# 328pv3.net
KiCad netlist of a schematic drawn in EAGLE
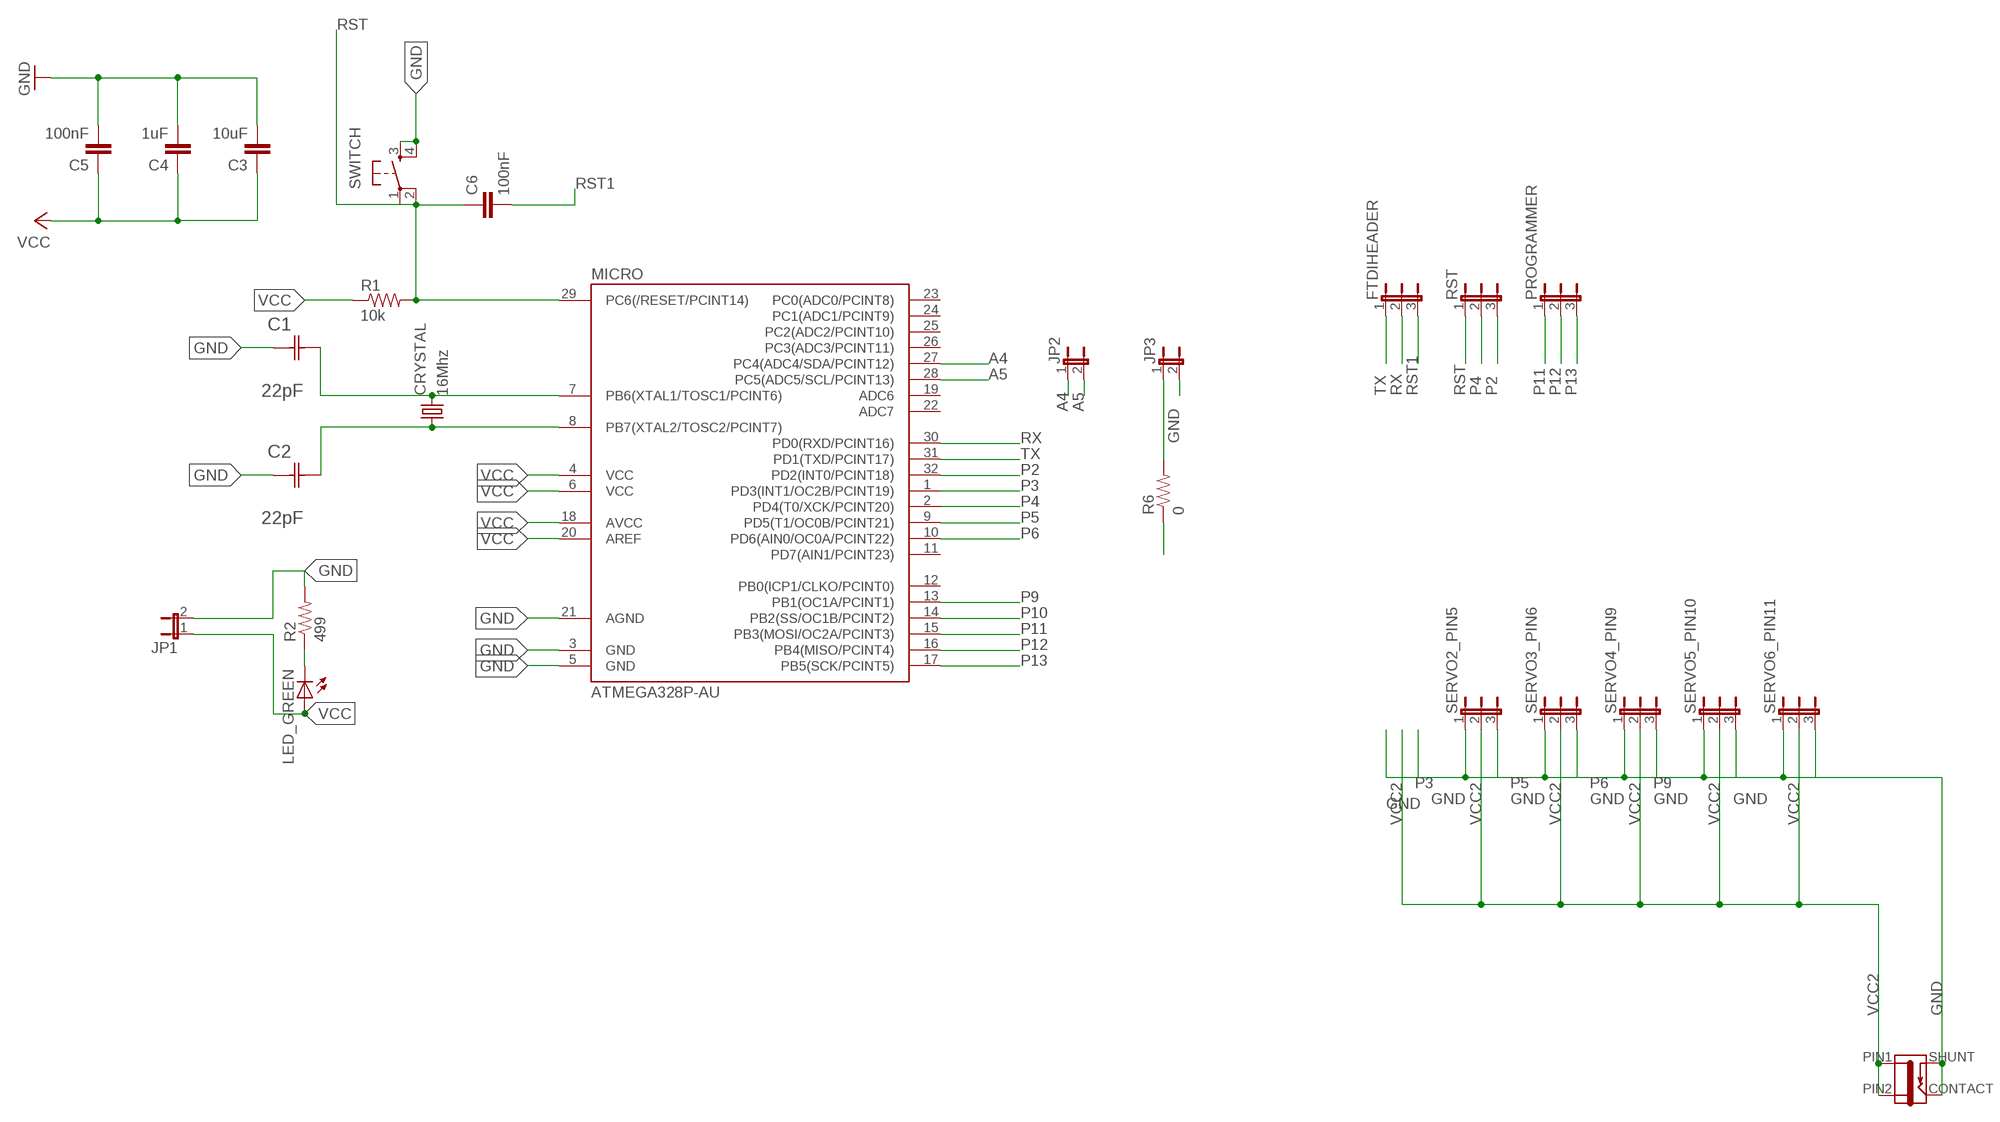
[diagram p0: schematic, sheet 1]

(export (version "E")
  (design (tool "Eeschema 10.0.6"))
  (components
    (comp (ref "C1")
      (value "22pF")
      (footprint "eagle-import:CAPC3216X178N")
      (fields (field (name "MPN") "0612ZC225MAT2A") (field (name "TOLERANCE") "±20%"))
      (libsource (lib "eagle-import") (part "0612ZC225MAT2A"))
    )
    (comp (ref "C2")
      (value "22pF")
      (footprint "eagle-import:CAPC3216X178N")
      (fields (field (name "MPN") "0612ZC225MAT2A") (field (name "TOLERANCE") "±20%"))
      (libsource (lib "eagle-import") (part "0612ZC225MAT2A"))
    )
    (comp (ref "C3")
      (value "10uF")
      (footprint "eagle-import:1206")
      (libsource (lib "eagle-import") (part "CAP1206"))
    )
    (comp (ref "C4")
      (value "1uF")
      (footprint "eagle-import:1206")
      (libsource (lib "eagle-import") (part "CAP1206"))
    )
    (comp (ref "C5")
      (value "100nF")
      (footprint "eagle-import:1206")
      (libsource (lib "eagle-import") (part "CAP1206"))
    )
    (comp (ref "C6")
      (value "100nF")
      (footprint "eagle-import:1206")
      (libsource (lib "eagle-import") (part "CAP1206"))
    )
    (comp (ref "CRYSTAL")
      (value "16Mhz")
      (footprint "eagle-import:CSM-7X-DU")
      (libsource (lib "eagle-import") (part "CSM-7X-DU"))
    )
    (comp (ref "FTDIHEADER")
      (value "JP2E")
      (footprint "eagle-import:JP2")
      (libsource (lib "eagle-import") (part "JP2E"))
    )
    (comp (ref "J1")
      (value "JACK-2.1MM")
      (footprint "eagle-import:PJ-002AH-SMT")
      (libsource (lib "eagle-import") (part "JACK-2.1MM"))
    )
    (comp (ref "JP1")
      (value "JP1E")
      (footprint "eagle-import:JP1")
      (libsource (lib "eagle-import") (part "JP1E"))
    )
    (comp (ref "JP2")
      (value "JP1E")
      (footprint "eagle-import:JP1")
      (libsource (lib "eagle-import") (part "JP1E"))
    )
    (comp (ref "JP3")
      (value "JP1E")
      (footprint "eagle-import:JP1")
      (libsource (lib "eagle-import") (part "JP1E"))
    )
    (comp (ref "LED_GREEN")
      (value "LED1206")
      (footprint "eagle-import:1206")
      (libsource (lib "eagle-import") (part "LED1206"))
    )
    (comp (ref "MICRO")
      (value "ATMEGA328P-AU")
      (footprint "eagle-import:TQFP32-08")
      (libsource (lib "eagle-import") (part "ATMEGA48/88/168-AU"))
    )
    (comp (ref "PROGRAMMER")
      (value "JP2E")
      (footprint "eagle-import:JP2")
      (libsource (lib "eagle-import") (part "JP2E"))
    )
    (comp (ref "R1")
      (value "10k")
      (footprint "eagle-import:1206")
      (libsource (lib "eagle-import") (part "RESISTOR1206"))
    )
    (comp (ref "R2")
      (value "499")
      (footprint "eagle-import:1206")
      (libsource (lib "eagle-import") (part "RESISTOR1206"))
    )
    (comp (ref "R6")
      (value "0")
      (footprint "eagle-import:1206")
      (libsource (lib "eagle-import") (part "RESISTOR1206"))
    )
    (comp (ref "RST")
      (value "JP2E")
      (footprint "eagle-import:JP2")
      (libsource (lib "eagle-import") (part "JP2E"))
    )
    (comp (ref "SERVO2_PIN5")
      (value "JP2E")
      (footprint "eagle-import:JP2")
      (libsource (lib "eagle-import") (part "JP2E"))
    )
    (comp (ref "SERVO3_PIN6")
      (value "JP2E")
      (footprint "eagle-import:JP2")
      (libsource (lib "eagle-import") (part "JP2E"))
    )
    (comp (ref "SERVO4_PIN9")
      (value "JP2E")
      (footprint "eagle-import:JP2")
      (libsource (lib "eagle-import") (part "JP2E"))
    )
    (comp (ref "SERVO5_PIN10")
      (value "JP2E")
      (footprint "eagle-import:JP2")
      (libsource (lib "eagle-import") (part "JP2E"))
    )
    (comp (ref "SERVO6_PIN11")
      (value "JP2E")
      (footprint "eagle-import:JP2")
      (libsource (lib "eagle-import") (part "JP2E"))
    )
    (comp (ref "SWITCH")
      (value "6MM_SWITCH6MM_SWITCH")
      (footprint "eagle-import:6MM_SWITCH")
      (libsource (lib "eagle-import") (part "6MM_SWITCH6MM_SWITCH"))
    )
  )
  (nets
    (net (code "1") (name "/A4") (class "Default")
      (node (ref "JP2") (pin "1") (pinfunction "1_1") (pintype "passive"))
      (node (ref "MICRO") (pin "27") (pinfunction "PC4(ADC4/SDA/PCINT12)_27") (pintype "bidirectional"))
    )
    (net (code "2") (name "/A5") (class "Default")
      (node (ref "JP2") (pin "2") (pinfunction "2_2") (pintype "passive"))
      (node (ref "MICRO") (pin "28") (pinfunction "PC5(ADC5/SCL/PCINT13)_28") (pintype "bidirectional"))
    )
    (net (code "3") (name "/P2") (class "Default")
      (node (ref "MICRO") (pin "32") (pinfunction "PD2(INT0/PCINT18)_32") (pintype "bidirectional"))
      (node (ref "RST") (pin "3") (pinfunction "3_3") (pintype "passive"))
    )
    (net (code "4") (name "/P3") (class "Default")
      (node (ref "MICRO") (pin "1") (pinfunction "PD3(INT1/OC2B/PCINT19)_1") (pintype "bidirectional"))
    )
    (net (code "5") (name "/P4") (class "Default")
      (node (ref "MICRO") (pin "2") (pinfunction "PD4(T0/XCK/PCINT20)_2") (pintype "bidirectional"))
      (node (ref "RST") (pin "2") (pinfunction "2_2") (pintype "passive"))
    )
    (net (code "6") (name "/P5") (class "Default")
      (node (ref "MICRO") (pin "9") (pinfunction "PD5(T1/OC0B/PCINT21)_9") (pintype "bidirectional"))
      (node (ref "SERVO2_PIN5") (pin "3") (pinfunction "3_3") (pintype "passive"))
    )
    (net (code "7") (name "/P6") (class "Default")
      (node (ref "MICRO") (pin "10") (pinfunction "PD6(AIN0/OC0A/PCINT22)_10") (pintype "bidirectional"))
      (node (ref "SERVO3_PIN6") (pin "3") (pinfunction "3_3") (pintype "passive"))
    )
    (net (code "8") (name "/P9") (class "Default")
      (node (ref "MICRO") (pin "13") (pinfunction "PB1(OC1A/PCINT1)_13") (pintype "bidirectional"))
      (node (ref "SERVO4_PIN9") (pin "3") (pinfunction "3_3") (pintype "passive"))
    )
    (net (code "9") (name "/P10") (class "Default")
      (node (ref "MICRO") (pin "14") (pinfunction "PB2(SS/OC1B/PCINT2)_14") (pintype "bidirectional"))
      (node (ref "SERVO5_PIN10") (pin "3") (pinfunction "3_3") (pintype "passive"))
    )
    (net (code "10") (name "/P11") (class "Default")
      (node (ref "MICRO") (pin "15") (pinfunction "PB3(MOSI/OC2A/PCINT3)_15") (pintype "bidirectional"))
      (node (ref "PROGRAMMER") (pin "1") (pinfunction "1_1") (pintype "passive"))
      (node (ref "SERVO6_PIN11") (pin "3") (pinfunction "3_3") (pintype "passive"))
    )
    (net (code "11") (name "/P12") (class "Default")
      (node (ref "MICRO") (pin "16") (pinfunction "PB4(MISO/PCINT4)_16") (pintype "bidirectional"))
      (node (ref "PROGRAMMER") (pin "2") (pinfunction "2_2") (pintype "passive"))
    )
    (net (code "12") (name "/P13") (class "Default")
      (node (ref "MICRO") (pin "17") (pinfunction "PB5(SCK/PCINT5)_17") (pintype "bidirectional"))
      (node (ref "PROGRAMMER") (pin "3") (pinfunction "3_3") (pintype "passive"))
    )
    (net (code "13") (name "/RST") (class "Default")
      (node (ref "C6") (pin "1") (pinfunction "1_1") (pintype "passive"))
      (node (ref "MICRO") (pin "29") (pinfunction "PC6(/RESET/PCINT14)_29") (pintype "bidirectional"))
      (node (ref "R1") (pin "2") (pinfunction "2_2") (pintype "passive"))
      (node (ref "RST") (pin "1") (pinfunction "1_1") (pintype "passive"))
      (node (ref "SWITCH") (pin "1") (pinfunction "P_1") (pintype "passive"))
      (node (ref "SWITCH") (pin "2") (pinfunction "P1_2") (pintype "passive"))
    )
    (net (code "14") (name "/RST1") (class "Default")
      (node (ref "C6") (pin "2") (pinfunction "2_2") (pintype "passive"))
      (node (ref "FTDIHEADER") (pin "3") (pinfunction "3_3") (pintype "passive"))
    )
    (net (code "15") (name "/RX") (class "Default")
      (node (ref "FTDIHEADER") (pin "2") (pinfunction "2_2") (pintype "passive"))
      (node (ref "MICRO") (pin "30") (pinfunction "PD0(RXD/PCINT16)_30") (pintype "bidirectional"))
    )
    (net (code "16") (name "/TX") (class "Default")
      (node (ref "FTDIHEADER") (pin "1") (pinfunction "1_1") (pintype "passive"))
      (node (ref "MICRO") (pin "31") (pinfunction "PD1(TXD/PCINT17)_31") (pintype "bidirectional"))
    )
    (net (code "17") (name "/VCC2") (class "Default")
      (node (ref "J1") (pin "PIN1") (pinfunction "PIN1_PIN1") (pintype "power_in"))
      (node (ref "J1") (pin "PIN2") (pinfunction "PIN2_PIN2") (pintype "power_in"))
      (node (ref "R6") (pin "1") (pinfunction "1_1") (pintype "passive"))
      (node (ref "SERVO2_PIN5") (pin "2") (pinfunction "2_2") (pintype "passive"))
      (node (ref "SERVO3_PIN6") (pin "2") (pinfunction "2_2") (pintype "passive"))
      (node (ref "SERVO4_PIN9") (pin "2") (pinfunction "2_2") (pintype "passive"))
      (node (ref "SERVO5_PIN10") (pin "2") (pinfunction "2_2") (pintype "passive"))
      (node (ref "SERVO6_PIN11") (pin "2") (pinfunction "2_2") (pintype "passive"))
    )
    (net (code "18") (name "GND") (class "Default")
      (node (ref "C1") (pin "1") (pinfunction "C1_1") (pintype "passive"))
      (node (ref "C2") (pin "1") (pinfunction "C1_1") (pintype "passive"))
      (node (ref "C3") (pin "2") (pinfunction "2_2") (pintype "passive"))
      (node (ref "C4") (pin "2") (pinfunction "2_2") (pintype "passive"))
      (node (ref "C5") (pin "2") (pinfunction "2_2") (pintype "passive"))
      (node (ref "J1") (pin "CONTACT") (pinfunction "CONTACT_CONTACT") (pintype "power_in"))
      (node (ref "J1") (pin "SHUNT") (pinfunction "SHUNT_SHUNT") (pintype "power_in"))
      (node (ref "JP1") (pin "2") (pinfunction "2_2") (pintype "passive"))
      (node (ref "JP3") (pin "2") (pinfunction "2_2") (pintype "passive"))
      (node (ref "MICRO") (pin "21") (pinfunction "AGND_21") (pintype "power_in"))
      (node (ref "MICRO") (pin "3") (pinfunction "GND_3") (pintype "power_in"))
      (node (ref "MICRO") (pin "5") (pinfunction "GND_5") (pintype "power_in"))
      (node (ref "R2") (pin "2") (pinfunction "2_2") (pintype "passive"))
      (node (ref "SERVO2_PIN5") (pin "1") (pinfunction "1_1") (pintype "passive"))
      (node (ref "SERVO3_PIN6") (pin "1") (pinfunction "1_1") (pintype "passive"))
      (node (ref "SERVO4_PIN9") (pin "1") (pinfunction "1_1") (pintype "passive"))
      (node (ref "SERVO5_PIN10") (pin "1") (pinfunction "1_1") (pintype "passive"))
      (node (ref "SERVO6_PIN11") (pin "1") (pinfunction "1_1") (pintype "passive"))
      (node (ref "SWITCH") (pin "3") (pinfunction "S_3") (pintype "passive"))
      (node (ref "SWITCH") (pin "4") (pinfunction "S1_4") (pintype "passive"))
    )
    (net (code "19") (name "Net-(C1-C2)") (class "Default")
      (node (ref "C1") (pin "2") (pinfunction "C2_2") (pintype "passive"))
      (node (ref "CRYSTAL") (pin "2") (pinfunction "2_2") (pintype "passive"))
      (node (ref "MICRO") (pin "7") (pinfunction "PB6(XTAL1/TOSC1/PCINT6)_7") (pintype "bidirectional"))
    )
    (net (code "20") (name "Net-(C2-C2)") (class "Default")
      (node (ref "C2") (pin "2") (pinfunction "C2_2") (pintype "passive"))
      (node (ref "CRYSTAL") (pin "1") (pinfunction "1_1") (pintype "passive"))
      (node (ref "MICRO") (pin "8") (pinfunction "PB7(XTAL2/TOSC2/PCINT7)_8") (pintype "bidirectional"))
    )
    (net (code "21") (name "Net-(JP3-Pad1)") (class "Default")
      (node (ref "JP3") (pin "1") (pinfunction "1_1") (pintype "passive"))
      (node (ref "R6") (pin "2") (pinfunction "2_2") (pintype "passive"))
    )
    (net (code "22") (name "Net-(LED_GREEN-C)") (class "Default")
      (node (ref "LED_GREEN") (pin "2") (pinfunction "C_2") (pintype "passive"))
      (node (ref "R2") (pin "1") (pinfunction "1_1") (pintype "passive"))
    )
    (net (code "23") (name "VCC") (class "Default")
      (node (ref "C3") (pin "1") (pinfunction "1_1") (pintype "passive"))
      (node (ref "C4") (pin "1") (pinfunction "1_1") (pintype "passive"))
      (node (ref "C5") (pin "1") (pinfunction "1_1") (pintype "passive"))
      (node (ref "JP1") (pin "1") (pinfunction "1_1") (pintype "passive"))
      (node (ref "LED_GREEN") (pin "1") (pinfunction "A_1") (pintype "passive"))
      (node (ref "MICRO") (pin "18") (pinfunction "AVCC_18") (pintype "passive"))
      (node (ref "MICRO") (pin "20") (pinfunction "AREF_20") (pintype "passive"))
      (node (ref "MICRO") (pin "4") (pinfunction "VCC_4") (pintype "power_in"))
      (node (ref "MICRO") (pin "6") (pinfunction "VCC_6") (pintype "power_in"))
      (node (ref "R1") (pin "1") (pinfunction "1_1") (pintype "passive"))
    )
    (net (code "24") (name "unconnected-(MICRO-ADC6-Pad19)") (class "Default")
      (node (ref "MICRO") (pin "19") (pinfunction "ADC6_19") (pintype "passive"))
    )
    (net (code "25") (name "unconnected-(MICRO-ADC7-Pad22)") (class "Default")
      (node (ref "MICRO") (pin "22") (pinfunction "ADC7_22") (pintype "passive"))
    )
    (net (code "26") (name "unconnected-(MICRO-PB0(ICP1{slash}CLKO{slash}PCINT0)-Pad12)") (class "Default")
      (node (ref "MICRO") (pin "12") (pinfunction "PB0(ICP1/CLKO/PCINT0)_12") (pintype "bidirectional"))
    )
    (net (code "27") (name "unconnected-(MICRO-PC0(ADC0{slash}PCINT8)-Pad23)") (class "Default")
      (node (ref "MICRO") (pin "23") (pinfunction "PC0(ADC0/PCINT8)_23") (pintype "bidirectional"))
    )
    (net (code "28") (name "unconnected-(MICRO-PC1(ADC1{slash}PCINT9)-Pad24)") (class "Default")
      (node (ref "MICRO") (pin "24") (pinfunction "PC1(ADC1/PCINT9)_24") (pintype "bidirectional"))
    )
    (net (code "29") (name "unconnected-(MICRO-PC2(ADC2{slash}PCINT10)-Pad25)") (class "Default")
      (node (ref "MICRO") (pin "25") (pinfunction "PC2(ADC2/PCINT10)_25") (pintype "bidirectional"))
    )
    (net (code "30") (name "unconnected-(MICRO-PC3(ADC3{slash}PCINT11)-Pad26)") (class "Default")
      (node (ref "MICRO") (pin "26") (pinfunction "PC3(ADC3/PCINT11)_26") (pintype "bidirectional"))
    )
    (net (code "31") (name "unconnected-(MICRO-PD7(AIN1{slash}PCINT23)-Pad11)") (class "Default")
      (node (ref "MICRO") (pin "11") (pinfunction "PD7(AIN1/PCINT23)_11") (pintype "bidirectional"))
    )
  )
)
